# 04-1_MCU.net
KiCad netlist of a schematic drawn in Altium Designer
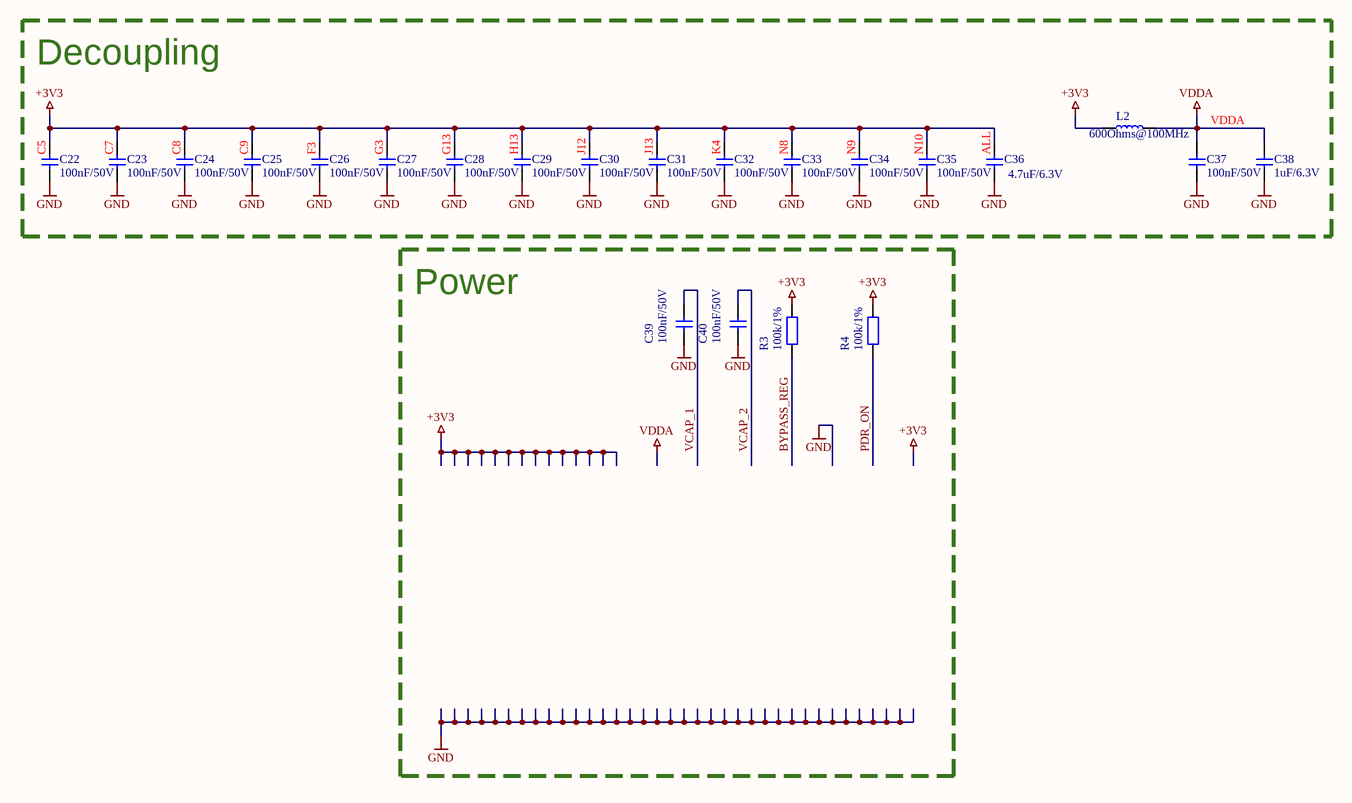
[diagram p0: 04-1 MCU.SchDoc]

(export (version "E")
  (design (tool "Eeschema 10.0.6"))
  (components
    (comp (ref "C22")
      (value "100nF/50V")
      (footprint "CAPC1005X06M-0402")
      (description "0.1 µF ±10% 50V Ceramic Capacitor X7R 0402 (1005 Metric)")
      (fields (field (name "MPN") "GRM155R71H104KE14D"))
      (libsource (lib "Symbol") (part "GRM155R71H104KE14D"))
    )
    (comp (ref "C23")
      (value "100nF/50V")
      (footprint "CAPC1005X06M-0402")
      (description "0.1 µF ±10% 50V Ceramic Capacitor X7R 0402 (1005 Metric)")
      (fields (field (name "MPN") "GRM155R71H104KE14D"))
      (libsource (lib "Symbol") (part "GRM155R71H104KE14D"))
    )
    (comp (ref "C24")
      (value "100nF/50V")
      (footprint "CAPC1005X06M-0402")
      (description "0.1 µF ±10% 50V Ceramic Capacitor X7R 0402 (1005 Metric)")
      (fields (field (name "MPN") "GRM155R71H104KE14D"))
      (libsource (lib "Symbol") (part "GRM155R71H104KE14D"))
    )
    (comp (ref "C25")
      (value "100nF/50V")
      (footprint "CAPC1005X06M-0402")
      (description "0.1 µF ±10% 50V Ceramic Capacitor X7R 0402 (1005 Metric)")
      (fields (field (name "MPN") "GRM155R71H104KE14D"))
      (libsource (lib "Symbol") (part "GRM155R71H104KE14D"))
    )
    (comp (ref "C26")
      (value "100nF/50V")
      (footprint "CAPC1005X06M-0402")
      (description "0.1 µF ±10% 50V Ceramic Capacitor X7R 0402 (1005 Metric)")
      (fields (field (name "MPN") "GRM155R71H104KE14D"))
      (libsource (lib "Symbol") (part "GRM155R71H104KE14D"))
    )
    (comp (ref "C27")
      (value "100nF/50V")
      (footprint "CAPC1005X06M-0402")
      (description "0.1 µF ±10% 50V Ceramic Capacitor X7R 0402 (1005 Metric)")
      (fields (field (name "MPN") "GRM155R71H104KE14D"))
      (libsource (lib "Symbol") (part "GRM155R71H104KE14D"))
    )
    (comp (ref "C28")
      (value "100nF/50V")
      (footprint "CAPC1005X06M-0402")
      (description "0.1 µF ±10% 50V Ceramic Capacitor X7R 0402 (1005 Metric)")
      (fields (field (name "MPN") "GRM155R71H104KE14D"))
      (libsource (lib "Symbol") (part "GRM155R71H104KE14D"))
    )
    (comp (ref "C29")
      (value "100nF/50V")
      (footprint "CAPC1005X06M-0402")
      (description "0.1 µF ±10% 50V Ceramic Capacitor X7R 0402 (1005 Metric)")
      (fields (field (name "MPN") "GRM155R71H104KE14D"))
      (libsource (lib "Symbol") (part "GRM155R71H104KE14D"))
    )
    (comp (ref "C30")
      (value "100nF/50V")
      (footprint "CAPC1005X06M-0402")
      (description "0.1 µF ±10% 50V Ceramic Capacitor X7R 0402 (1005 Metric)")
      (fields (field (name "MPN") "GRM155R71H104KE14D"))
      (libsource (lib "Symbol") (part "GRM155R71H104KE14D"))
    )
    (comp (ref "C31")
      (value "100nF/50V")
      (footprint "CAPC1005X06M-0402")
      (description "0.1 µF ±10% 50V Ceramic Capacitor X7R 0402 (1005 Metric)")
      (fields (field (name "MPN") "GRM155R71H104KE14D"))
      (libsource (lib "Symbol") (part "GRM155R71H104KE14D"))
    )
    (comp (ref "C32")
      (value "100nF/50V")
      (footprint "CAPC1005X06M-0402")
      (description "0.1 µF ±10% 50V Ceramic Capacitor X7R 0402 (1005 Metric)")
      (fields (field (name "MPN") "GRM155R71H104KE14D"))
      (libsource (lib "Symbol") (part "GRM155R71H104KE14D"))
    )
    (comp (ref "C33")
      (value "100nF/50V")
      (footprint "CAPC1005X06M-0402")
      (description "0.1 µF ±10% 50V Ceramic Capacitor X7R 0402 (1005 Metric)")
      (fields (field (name "MPN") "GRM155R71H104KE14D"))
      (libsource (lib "Symbol") (part "GRM155R71H104KE14D"))
    )
    (comp (ref "C34")
      (value "100nF/50V")
      (footprint "CAPC1005X06M-0402")
      (description "0.1 µF ±10% 50V Ceramic Capacitor X7R 0402 (1005 Metric)")
      (fields (field (name "MPN") "GRM155R71H104KE14D"))
      (libsource (lib "Symbol") (part "GRM155R71H104KE14D"))
    )
    (comp (ref "C35")
      (value "100nF/50V")
      (footprint "CAPC1005X06M-0402")
      (description "0.1 µF ±10% 50V Ceramic Capacitor X7R 0402 (1005 Metric)")
      (fields (field (name "MPN") "GRM155R71H104KE14D"))
      (libsource (lib "Symbol") (part "GRM155R71H104KE14D"))
    )
    (comp (ref "C36")
      (value "4.7uF/6.3V")
      (footprint "CAPC1005X06M-0402")
      (description "4.7 µF ±20% 6.3V Ceramic Capacitor X5R 0402 (1005 Metric)")
      (fields (field (name "MPN") "GRM155R60J475ME47D"))
      (libsource (lib "Symbol") (part "GRM155R60J475ME47D"))
    )
    (comp (ref "C37")
      (value "100nF/50V")
      (footprint "CAPC1005X06M-0402")
      (description "0.1 µF ±10% 50V Ceramic Capacitor X7R 0402 (1005 Metric)")
      (fields (field (name "MPN") "GRM155R71H104KE14D"))
      (libsource (lib "Symbol") (part "GRM155R71H104KE14D"))
    )
    (comp (ref "C38")
      (value "1uF/6.3V")
      (footprint "CAPC1005X06M-0402")
      (description "1 µF ±10% 6.3V Ceramic Capacitor X7R 0402 (1005 Metric)")
      (fields (field (name "MPN") "GRM155R70J105KA12J"))
      (libsource (lib "Symbol") (part "GRM155R70J105KA12J"))
    )
    (comp (ref "C39")
      (value "100nF/50V")
      (footprint "CAPC1005X06M-0402")
      (description "0.1 µF ±10% 50V Ceramic Capacitor X7R 0402 (1005 Metric)")
      (fields (field (name "MPN") "GRM155R71H104KE14D"))
      (libsource (lib "Symbol") (part "GRM155R71H104KE14D"))
    )
    (comp (ref "C40")
      (value "100nF/50V")
      (footprint "CAPC1005X06M-0402")
      (description "0.1 µF ±10% 50V Ceramic Capacitor X7R 0402 (1005 Metric)")
      (fields (field (name "MPN") "GRM155R71H104KE14D"))
      (libsource (lib "Symbol") (part "GRM155R71H104KE14D"))
    )
    (comp (ref "L2")
      (value "600Ohms@100MHz")
      (footprint "INDC1005X06M-0402")
      (description "600 Ohms @ 100 MHz 1 Ferrite Bead 0402 (1005 Metric) 300mA 520mOhm")
      (fields (field (name "MPN") "BLM15AG601SN1D"))
      (libsource (lib "Symbol") (part "BLM15AG601SN1D"))
    )
    (comp (ref "R3")
      (value "100k/1%")
      (footprint "RESC1005X04M-0402")
      (description "100 kOhms ±1% 0.063W, 1/16W Chip Resistor 0402 (1005 Metric) Moisture Resistant Thick Film")
      (fields (field (name "MPN") "RC0402FR-07100KL"))
      (libsource (lib "Symbol") (part "RC0402FR-07100KL"))
    )
    (comp (ref "R4")
      (value "100k/1%")
      (footprint "RESC1005X04M-0402")
      (description "100 kOhms ±1% 0.063W, 1/16W Chip Resistor 0402 (1005 Metric) Moisture Resistant Thick Film")
      (fields (field (name "MPN") "RC0402FR-07100KL"))
      (libsource (lib "Symbol") (part "RC0402FR-07100KL"))
    )
  )
  (nets
    (net (code "1") (name "+3V3") (class "Default")
      (node (ref "C22") (pin "2") (pinfunction "2_2") (pintype "passive"))
      (node (ref "C23") (pin "2") (pinfunction "2_2") (pintype "passive"))
      (node (ref "C24") (pin "2") (pinfunction "2_2") (pintype "passive"))
      (node (ref "C25") (pin "2") (pinfunction "2_2") (pintype "passive"))
      (node (ref "C26") (pin "2") (pinfunction "2_2") (pintype "passive"))
      (node (ref "C27") (pin "2") (pinfunction "2_2") (pintype "passive"))
      (node (ref "C28") (pin "2") (pinfunction "2_2") (pintype "passive"))
      (node (ref "C29") (pin "2") (pinfunction "2_2") (pintype "passive"))
      (node (ref "C30") (pin "2") (pinfunction "2_2") (pintype "passive"))
      (node (ref "C31") (pin "2") (pinfunction "2_2") (pintype "passive"))
      (node (ref "C32") (pin "2") (pinfunction "2_2") (pintype "passive"))
      (node (ref "C33") (pin "2") (pinfunction "2_2") (pintype "passive"))
      (node (ref "C34") (pin "2") (pinfunction "2_2") (pintype "passive"))
      (node (ref "C35") (pin "2") (pinfunction "2_2") (pintype "passive"))
      (node (ref "C36") (pin "2") (pinfunction "2_2") (pintype "passive"))
      (node (ref "L2") (pin "1") (pinfunction "1_1") (pintype "passive"))
      (node (ref "R3") (pin "1") (pinfunction "1_1") (pintype "passive"))
      (node (ref "R4") (pin "1") (pinfunction "1_1") (pintype "passive"))
    )
    (net (code "2") (name "/BYPASS_REG") (class "Default")
      (node (ref "R3") (pin "2") (pinfunction "2_2") (pintype "passive"))
    )
    (net (code "3") (name "/PDR_ON") (class "Default")
      (node (ref "R4") (pin "2") (pinfunction "2_2") (pintype "passive"))
    )
    (net (code "4") (name "/VCAP_1") (class "Default")
      (node (ref "C39") (pin "2") (pinfunction "2_2") (pintype "passive"))
    )
    (net (code "5") (name "/VCAP_2") (class "Default")
      (node (ref "C40") (pin "2") (pinfunction "2_2") (pintype "passive"))
    )
    (net (code "6") (name "GND") (class "Default")
      (node (ref "C22") (pin "1") (pinfunction "1_1") (pintype "passive"))
      (node (ref "C23") (pin "1") (pinfunction "1_1") (pintype "passive"))
      (node (ref "C24") (pin "1") (pinfunction "1_1") (pintype "passive"))
      (node (ref "C25") (pin "1") (pinfunction "1_1") (pintype "passive"))
      (node (ref "C26") (pin "1") (pinfunction "1_1") (pintype "passive"))
      (node (ref "C27") (pin "1") (pinfunction "1_1") (pintype "passive"))
      (node (ref "C28") (pin "1") (pinfunction "1_1") (pintype "passive"))
      (node (ref "C29") (pin "1") (pinfunction "1_1") (pintype "passive"))
      (node (ref "C30") (pin "1") (pinfunction "1_1") (pintype "passive"))
      (node (ref "C31") (pin "1") (pinfunction "1_1") (pintype "passive"))
      (node (ref "C32") (pin "1") (pinfunction "1_1") (pintype "passive"))
      (node (ref "C33") (pin "1") (pinfunction "1_1") (pintype "passive"))
      (node (ref "C34") (pin "1") (pinfunction "1_1") (pintype "passive"))
      (node (ref "C35") (pin "1") (pinfunction "1_1") (pintype "passive"))
      (node (ref "C36") (pin "1") (pinfunction "1_1") (pintype "passive"))
      (node (ref "C37") (pin "1") (pinfunction "1_1") (pintype "passive"))
      (node (ref "C38") (pin "1") (pinfunction "1_1") (pintype "passive"))
      (node (ref "C39") (pin "1") (pinfunction "1_1") (pintype "passive"))
      (node (ref "C40") (pin "1") (pinfunction "1_1") (pintype "passive"))
    )
    (net (code "7") (name "VDDA") (class "Default")
      (node (ref "C37") (pin "2") (pinfunction "2_2") (pintype "passive"))
      (node (ref "C38") (pin "2") (pinfunction "2_2") (pintype "passive"))
      (node (ref "L2") (pin "2") (pinfunction "2_2") (pintype "passive"))
    )
  )
)
